# power.net
KiCad netlist of a schematic drawn in Altium Designer
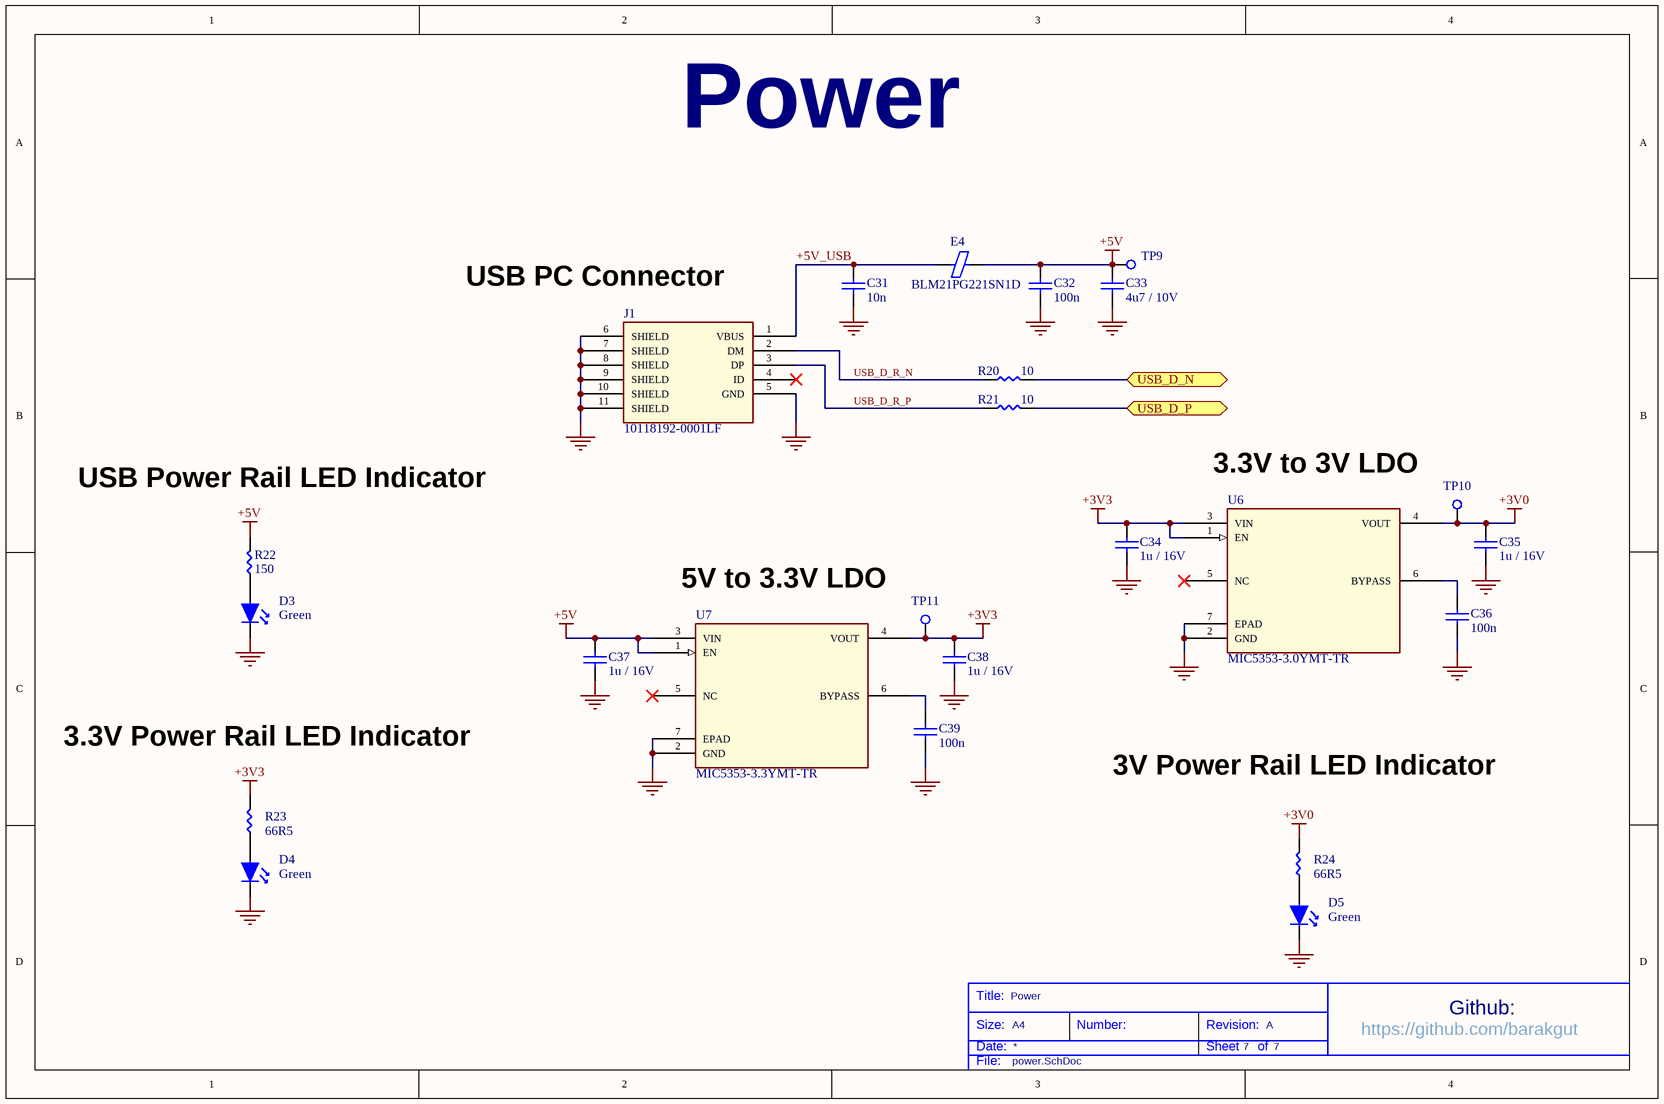
[diagram p0: power.SchDoc]

(export (version "E")
  (design (tool "Eeschema 10.0.6"))
  (components
    (comp (ref "C31")
      (value "10n")
      (footprint "C0402")
      (fields
        (field (name "MANUFACTURER") "TDK")
        (field (name "TOLERANCE") "±10%")
        (field (name "PCN PART NUMBER") "MLCC Part Number Change 30/Nov/2012")
      )
      (libsource (lib "rookieboard_symbols") (part "CGA2B3X7R1V103K050BB"))
    )
    (comp (ref "C32")
      (value "100n")
      (footprint "C0402")
      (fields
        (field (name "MANUFACTURER") "TDK")
        (field (name "PCN PART NUMBER") "MLCC Part Number Change 30/Nov/2012")
        (field (name "TOLERANCE") "±10%")
      )
      (libsource (lib "rookieboard_symbols") (part "CGA2B3X7R1E104K050BB"))
    )
    (comp (ref "C33")
      (value "4u7 / 10V")
      (footprint "C0805")
      (fields
        (field (name "MANUFACTURER") "TDK")
        (field (name "TOLERANCE") "±10%")
        (field (name "MANUFACTURER PART NUMBER") "C2012X7R1A475K085AC")
      )
      (libsource (lib "rookieboard_symbols") (part "C2012X7R1A475K085AC"))
    )
    (comp (ref "C34")
      (value "1u / 16V")
      (footprint "C0805")
      (description "Multilayer Ceramic Capacitors MLCC - SMD/SMT 16volts 1uF X7R 10%")
      (fields (field (name "MANUFACTURER") "KEMET") (field (name "VOLTAGE") "16 Vdc"))
      (libsource (lib "rookieboard_symbols") (part "C0805C105K4RAC7800"))
    )
    (comp (ref "C35")
      (value "1u / 16V")
      (footprint "C0805")
      (description "Multilayer Ceramic Capacitors MLCC - SMD/SMT 16volts 1uF X7R 10%")
      (fields (field (name "MANUFACTURER") "KEMET") (field (name "VOLTAGE") "16 Vdc"))
      (libsource (lib "rookieboard_symbols") (part "C0805C105K4RAC7800"))
    )
    (comp (ref "C36")
      (value "100n")
      (footprint "C0402")
      (fields
        (field (name "MANUFACTURER") "TDK")
        (field (name "PCN PART NUMBER") "MLCC Part Number Change 30/Nov/2012")
        (field (name "TOLERANCE") "±10%")
      )
      (libsource (lib "rookieboard_symbols") (part "CGA2B3X7R1E104K050BB"))
    )
    (comp (ref "C37")
      (value "1u / 16V")
      (footprint "C0805")
      (description "Multilayer Ceramic Capacitors MLCC - SMD/SMT 16volts 1uF X7R 10%")
      (fields (field (name "MANUFACTURER") "KEMET") (field (name "VOLTAGE") "16 Vdc"))
      (libsource (lib "rookieboard_symbols") (part "C0805C105K4RAC7800"))
    )
    (comp (ref "C38")
      (value "1u / 16V")
      (footprint "C0805")
      (description "Multilayer Ceramic Capacitors MLCC - SMD/SMT 16volts 1uF X7R 10%")
      (fields (field (name "MANUFACTURER") "KEMET") (field (name "VOLTAGE") "16 Vdc"))
      (libsource (lib "rookieboard_symbols") (part "C0805C105K4RAC7800"))
    )
    (comp (ref "C39")
      (value "100n")
      (footprint "C0402")
      (fields
        (field (name "MANUFACTURER") "TDK")
        (field (name "PCN PART NUMBER") "MLCC Part Number Change 30/Nov/2012")
        (field (name "TOLERANCE") "±10%")
      )
      (libsource (lib "rookieboard_symbols") (part "CGA2B3X7R1E104K050BB"))
    )
    (comp (ref "D3")
      (value "Green")
      (footprint "150141VS73100_LED")
      (description "WURTH ELEKTRONIK   150141VS73100   LED, GREEN, 90MCD, 570NM")
      (fields
        (field (name "MANUFACTURER") "Wurth Electronics")
        (field (name "MANUFACTURER PART NUMBER") "150141VS73100")
      )
      (libsource (lib "rookieboard_symbols") (part "150141VS73100"))
    )
    (comp (ref "D4")
      (value "Green")
      (footprint "150141VS73100_LED")
      (description "WURTH ELEKTRONIK   150141VS73100   LED, GREEN, 90MCD, 570NM")
      (fields
        (field (name "MANUFACTURER") "Wurth Electronics")
        (field (name "MANUFACTURER PART NUMBER") "150141VS73100")
      )
      (libsource (lib "rookieboard_symbols") (part "150141VS73100"))
    )
    (comp (ref "D5")
      (value "Green")
      (footprint "150141VS73100_LED")
      (description "WURTH ELEKTRONIK   150141VS73100   LED, GREEN, 90MCD, 570NM")
      (fields
        (field (name "MANUFACTURER") "Wurth Electronics")
        (field (name "MANUFACTURER PART NUMBER") "150141VS73100")
      )
      (libsource (lib "rookieboard_symbols") (part "150141VS73100"))
    )
    (comp (ref "E4")
      (value "BLM21PG221SN1D")
      (footprint "R0805")
      (description "FERRITE CHIP 220 OHM 0805")
      (fields (field (name "MANUFACTURER") "Murata"))
      (libsource (lib "rookieboard_symbols") (part "BLM21PG221SN1D"))
    )
    (comp (ref "J1")
      (value "10118192-0001LF")
      (footprint "10118192-0001LF")
      (description "USB - micro B USB 2.0 Receptacle Connector 5 Position Surface Mount, Right Angle, Horizontal")
      (fields
        (field (name "MANUFACTURER") "Amphenol FCI")
        (field (name "MANUFACTURER PART NUMBER") "10118192-0001LF")
      )
      (libsource (lib "rookieboard_symbols") (part "10118192-0001LF"))
    )
    (comp (ref "R20")
      (value "10")
      (footprint "R0402")
      (description "RES SMD 10 OHM 1% 1/16W 0402")
      (fields (field (name "MANUFACTURER") "Yageo") (field (name "TOLERANCE") "1 %"))
      (libsource (lib "rookieboard_symbols") (part "RC0402FR-0710RL"))
    )
    (comp (ref "R21")
      (value "10")
      (footprint "R0402")
      (description "RES SMD 10 OHM 1% 1/16W 0402")
      (fields (field (name "MANUFACTURER") "Yageo") (field (name "TOLERANCE") "1 %"))
      (libsource (lib "rookieboard_symbols") (part "RC0402FR-0710RL"))
    )
    (comp (ref "R22")
      (value "150")
      (footprint "R0805")
      (description "Thick Film Resistors - SMD 1/8W 150ohm 1%")
      (fields (field (name "MANUFACTURER") "Yageo") (field (name "TOLERANCE") "1 %"))
      (libsource (lib "rookieboard_symbols") (part "AC0805FR-07150RL"))
    )
    (comp (ref "R23")
      (value "66R5")
      (footprint "R0805")
      (description "Thick Film Resistors - SMD 66.5 OHM 1%")
      (fields (field (name "MANUFACTURER") "Yageo") (field (name "TOLERANCE") "1 %"))
      (libsource (lib "rookieboard_symbols") (part "RC0805FR-0766R5L"))
    )
    (comp (ref "R24")
      (value "66R5")
      (footprint "R0805")
      (description "Thick Film Resistors - SMD 66.5 OHM 1%")
      (fields (field (name "MANUFACTURER") "Yageo") (field (name "TOLERANCE") "1 %"))
      (libsource (lib "rookieboard_symbols") (part "RC0805FR-0766R5L"))
    )
    (comp (ref "TP9")
      (value "Test Pad 1mm")
      (footprint "TP_1MM")
      (libsource (lib "rookieboard_symbols") (part "TEST_PAD_1mm"))
    )
    (comp (ref "TP10")
      (value "Test Pad 1mm")
      (footprint "TP_1MM")
      (libsource (lib "rookieboard_symbols") (part "TEST_PAD_1mm"))
    )
    (comp (ref "TP11")
      (value "Test Pad 1mm")
      (footprint "TP_1MM")
      (libsource (lib "rookieboard_symbols") (part "TEST_PAD_1mm"))
    )
    (comp (ref "U6")
      (value "MIC5353-3.0YMT-TR")
      (footprint "6-MLF")
      (description "6Vin, Single 500mA ULDO, 6 UDFN 1.6x1.6x0.6mm T/R")
      (fields (field (name "MANUFACTURER") "Microchip"))
      (libsource (lib "rookieboard_symbols") (part "MIC5353-3.0YMT-TR"))
    )
    (comp (ref "U7")
      (value "MIC5353-3.3YMT-TR")
      (footprint "6-MLF")
      (fields (field (name "MANUFACTURER") "Microchip"))
      (libsource (lib "rookieboard_symbols") (part "MIC5353-3.3YMT-TR"))
    )
  )
  (nets
    (net (code "1") (name "+3V0") (class "Default")
      (node (ref "C35") (pin "2") (pinfunction "2_2") (pintype "passive"))
      (node (ref "R24") (pin "2") (pinfunction "2_2") (pintype "passive"))
      (node (ref "TP10") (pin "1") (pinfunction "1_1") (pintype "passive"))
      (node (ref "U6") (pin "4") (pinfunction "VOUT_4") (pintype "power_in"))
    )
    (net (code "2") (name "+3V3") (class "Default")
      (node (ref "C34") (pin "2") (pinfunction "2_2") (pintype "passive"))
      (node (ref "C38") (pin "2") (pinfunction "2_2") (pintype "passive"))
      (node (ref "R23") (pin "2") (pinfunction "2_2") (pintype "passive"))
      (node (ref "TP11") (pin "1") (pinfunction "1_1") (pintype "passive"))
      (node (ref "U6") (pin "1") (pinfunction "EN_1") (pintype "input"))
      (node (ref "U6") (pin "3") (pinfunction "VIN_3") (pintype "power_in"))
      (node (ref "U7") (pin "4") (pinfunction "VOUT_4") (pintype "power_in"))
    )
    (net (code "3") (name "+5V") (class "Default")
      (node (ref "C32") (pin "2") (pinfunction "2_2") (pintype "passive"))
      (node (ref "C33") (pin "2") (pinfunction "2_2") (pintype "passive"))
      (node (ref "C37") (pin "2") (pinfunction "2_2") (pintype "passive"))
      (node (ref "E4") (pin "2") (pinfunction "2_2") (pintype "passive"))
      (node (ref "R22") (pin "2") (pinfunction "2_2") (pintype "passive"))
      (node (ref "TP9") (pin "1") (pinfunction "1_1") (pintype "passive"))
      (node (ref "U7") (pin "1") (pinfunction "EN_1") (pintype "input"))
      (node (ref "U7") (pin "3") (pinfunction "VIN_3") (pintype "power_in"))
    )
    (net (code "4") (name "/+5V_USB") (class "Default")
      (node (ref "C31") (pin "2") (pinfunction "2_2") (pintype "passive"))
      (node (ref "E4") (pin "1") (pinfunction "1_1") (pintype "passive"))
      (node (ref "J1") (pin "1") (pinfunction "VBUS_1") (pintype "power_in"))
    )
    (net (code "5") (name "/USB_D_N") (class "Default")
      (node (ref "R20") (pin "2") (pinfunction "2_2") (pintype "passive"))
    )
    (net (code "6") (name "/USB_D_P") (class "Default")
      (node (ref "R21") (pin "2") (pinfunction "2_2") (pintype "passive"))
    )
    (net (code "7") (name "/USB_D_R_N") (class "Default")
      (node (ref "J1") (pin "2") (pinfunction "DM_2") (pintype "passive"))
      (node (ref "R20") (pin "1") (pinfunction "1_1") (pintype "passive"))
    )
    (net (code "8") (name "/USB_D_R_P") (class "Default")
      (node (ref "J1") (pin "3") (pinfunction "DP_3") (pintype "passive"))
      (node (ref "R21") (pin "1") (pinfunction "1_1") (pintype "passive"))
    )
    (net (code "9") (name "GND") (class "Default")
      (node (ref "C31") (pin "1") (pinfunction "1_1") (pintype "passive"))
      (node (ref "C32") (pin "1") (pinfunction "1_1") (pintype "passive"))
      (node (ref "C33") (pin "1") (pinfunction "1_1") (pintype "passive"))
      (node (ref "C34") (pin "1") (pinfunction "1_1") (pintype "passive"))
      (node (ref "C35") (pin "1") (pinfunction "1_1") (pintype "passive"))
      (node (ref "C36") (pin "1") (pinfunction "1_1") (pintype "passive"))
      (node (ref "C37") (pin "1") (pinfunction "1_1") (pintype "passive"))
      (node (ref "C38") (pin "1") (pinfunction "1_1") (pintype "passive"))
      (node (ref "C39") (pin "1") (pinfunction "1_1") (pintype "passive"))
      (node (ref "D3") (pin "1") (pinfunction "K_1") (pintype "passive"))
      (node (ref "D4") (pin "1") (pinfunction "K_1") (pintype "passive"))
      (node (ref "D5") (pin "1") (pinfunction "K_1") (pintype "passive"))
      (node (ref "J1") (pin "10") (pinfunction "SHIELD_10") (pintype "passive"))
      (node (ref "J1") (pin "11") (pinfunction "SHIELD_11") (pintype "passive"))
      (node (ref "J1") (pin "5") (pinfunction "GND_5") (pintype "power_in"))
      (node (ref "J1") (pin "6") (pinfunction "SHIELD_6") (pintype "passive"))
      (node (ref "J1") (pin "7") (pinfunction "SHIELD_7") (pintype "passive"))
      (node (ref "J1") (pin "8") (pinfunction "SHIELD_8") (pintype "passive"))
      (node (ref "J1") (pin "9") (pinfunction "SHIELD_9") (pintype "passive"))
      (node (ref "U6") (pin "2") (pinfunction "GND_2") (pintype "power_in"))
      (node (ref "U6") (pin "7") (pinfunction "EPAD_7") (pintype "power_in"))
      (node (ref "U7") (pin "2") (pinfunction "GND_2") (pintype "power_in"))
      (node (ref "U7") (pin "7") (pinfunction "EPAD_7") (pintype "power_in"))
    )
    (net (code "10") (name "Net-(D3-A)") (class "Default")
      (node (ref "D3") (pin "2") (pinfunction "A_2") (pintype "passive"))
      (node (ref "R22") (pin "1") (pinfunction "1_1") (pintype "passive"))
    )
    (net (code "11") (name "Net-(D4-A)") (class "Default")
      (node (ref "D4") (pin "2") (pinfunction "A_2") (pintype "passive"))
      (node (ref "R23") (pin "1") (pinfunction "1_1") (pintype "passive"))
    )
    (net (code "12") (name "Net-(D5-A)") (class "Default")
      (node (ref "D5") (pin "2") (pinfunction "A_2") (pintype "passive"))
      (node (ref "R24") (pin "1") (pinfunction "1_1") (pintype "passive"))
    )
    (net (code "13") (name "Net-(U6-BYPASS)") (class "Default")
      (node (ref "C36") (pin "2") (pinfunction "2_2") (pintype "passive"))
      (node (ref "U6") (pin "6") (pinfunction "BYPASS_6") (pintype "passive"))
    )
    (net (code "14") (name "Net-(U7-BYPASS)") (class "Default")
      (node (ref "C39") (pin "2") (pinfunction "2_2") (pintype "passive"))
      (node (ref "U7") (pin "6") (pinfunction "BYPASS_6") (pintype "passive"))
    )
    (net (code "15") (name "unconnected-(J1-ID-Pad4)") (class "Default")
      (node (ref "J1") (pin "4") (pinfunction "ID_4") (pintype "passive+no_connect"))
    )
    (net (code "16") (name "unconnected-(U6-NC-Pad5)") (class "Default")
      (node (ref "U6") (pin "5") (pinfunction "NC_5") (pintype "passive+no_connect"))
    )
    (net (code "17") (name "unconnected-(U7-NC-Pad5)") (class "Default")
      (node (ref "U7") (pin "5") (pinfunction "NC_5") (pintype "passive+no_connect"))
    )
  )
)
